# ExosLPBatt.net
KiCad netlist of a schematic drawn in EAGLE
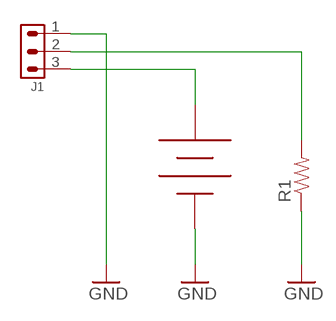
[diagram p0: schematic, sheet 1]

(export (version "E")
  (design (tool "Eeschema 10.0.6"))
  (components
    (comp (ref "J1")
      (value "CONN_3X1_JST_PA")
      (footprint "eagle-import:CONN_3X1_JST_PA")
      (libsource (lib "eagle-import") (part "CONN_3X1_JST_PA"))
    )
    (comp (ref "R1")
      (value "0603_RES")
      (footprint "eagle-import:0603")
      (libsource (lib "eagle-import") (part "0603_RES"))
    )
    (comp (ref "U$2")
      (value "14500_KEYSTONE_1024")
      (footprint "eagle-import:14500_KEYSTONE_1024")
      (libsource (lib "eagle-import") (part "14500_KEYSTONE_1024"))
    )
  )
  (nets
    (net (code "1") (name "GND") (class "Default")
      (node (ref "J1") (pin "1") (pinfunction "1_1") (pintype "bidirectional"))
      (node (ref "R1") (pin "P$1") (pinfunction "1_P$1") (pintype "passive"))
      (node (ref "U$2") (pin "NEG") (pinfunction "NEG_NEG") (pintype "bidirectional"))
    )
    (net (code "2") (name "Net-(J1-Pad3)") (class "Default")
      (node (ref "J1") (pin "3") (pinfunction "3_3") (pintype "bidirectional"))
      (node (ref "U$2") (pin "POS") (pinfunction "POS_POS") (pintype "bidirectional"))
    )
    (net (code "3") (name "Net-(R1-2)") (class "Default")
      (node (ref "J1") (pin "2") (pinfunction "2_2") (pintype "bidirectional"))
      (node (ref "R1") (pin "P$2") (pinfunction "2_P$2") (pintype "passive"))
    )
  )
)
